# Communications.net
KiCad netlist of a schematic drawn in Altium Designer
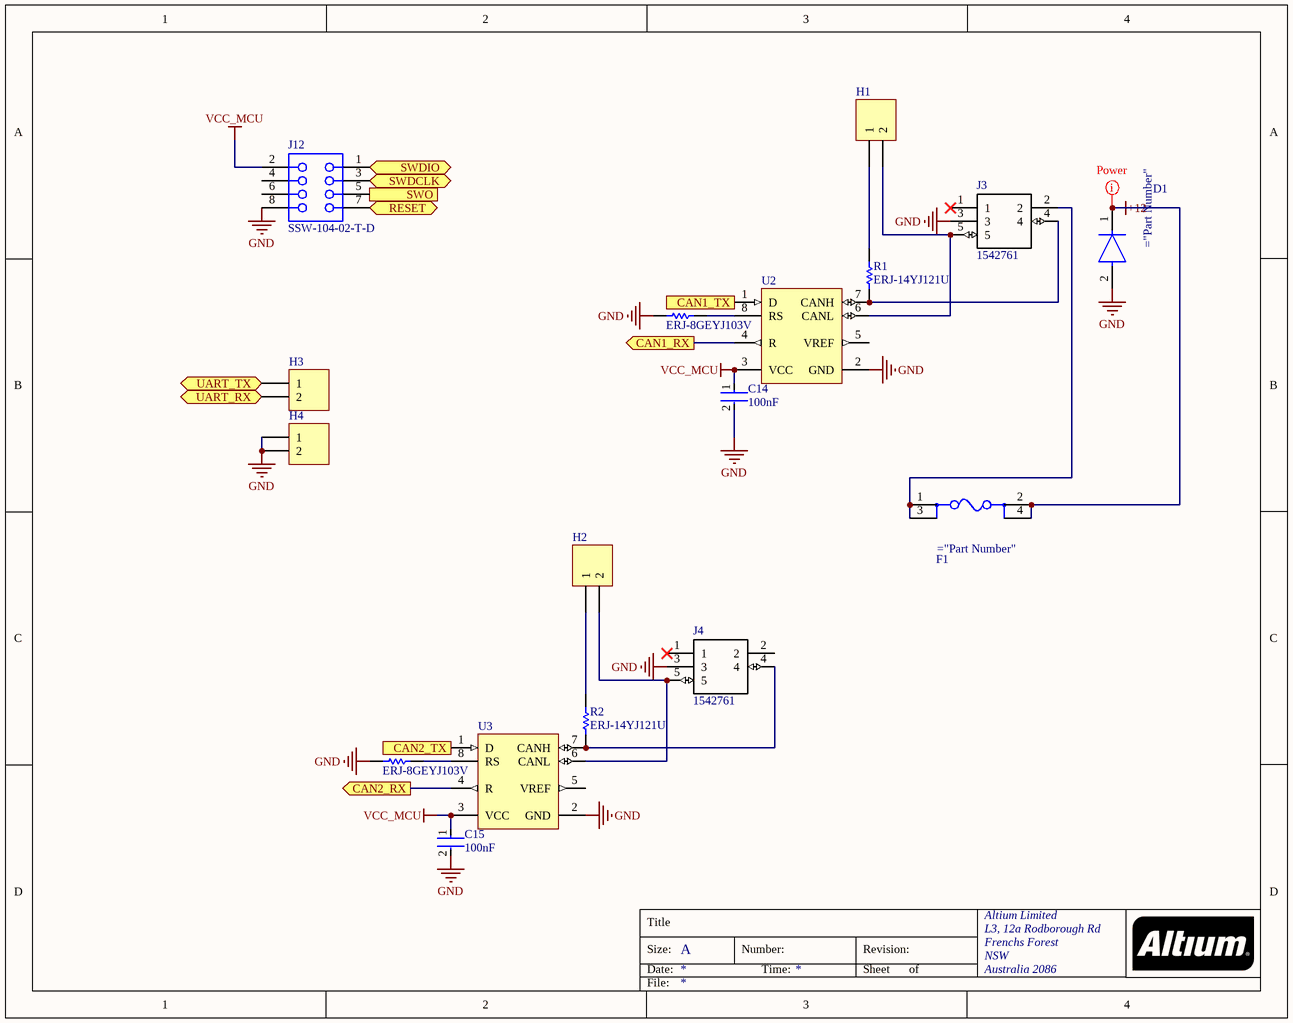
[diagram p0: Communications.SchDoc]

(export (version "E")
  (design (tool "Eeschema 10.0.6"))
  (components
    (comp (ref "C14")
      (value "100nF")
      (footprint "Kemet_C0603_IPC_A")
      (description "CAP CER 0.1UF 100NF 50V X7R 0603 C0603C104K5RACTU")
      (libsource (lib "UNK_Kemet_C0603C104K5RACTU_eec") (part "C0603C104K5RACTU"))
    )
    (comp (ref "C15")
      (value "100nF")
      (footprint "Kemet_C0603_IPC_A")
      (description "CAP CER 0.1UF 100NF 50V X7R 0603 C0603C104K5RACTU")
      (libsource (lib "UNK_Kemet_C0603C104K5RACTU_eec") (part "C0603C104K5RACTU"))
    )
    (comp (ref "D1")
      (value "S1J-13-F")
      (footprint "Diodes_SMA_0")
      (libsource (lib "Diode_Diodes_S1J-13-F_eec") (part "S1J-13-F"))
    )
    (comp (ref "F1")
      (value "3557-2")
      (footprint "Keystone_3557-2_0")
      (libsource (lib "Fuse_Keystone_3557-2_eec") (part "3557-2"))
    )
    (comp (ref "H1")
      (value "Header 0")
      (footprint "HDR1X2")
      (description "Header, 2-Pin")
      (fields (field (name "PUBLISHER") "Altium Limited"))
      (libsource (lib "") (part "Header 2_1"))
    )
    (comp (ref "H2")
      (value "Header 0")
      (footprint "HDR1X2")
      (description "Header, 2-Pin")
      (fields (field (name "PUBLISHER") "Altium Limited"))
      (libsource (lib "") (part "Header 2_1"))
    )
    (comp (ref "H3")
      (value "Header 0")
      (footprint "HDR1X2")
      (description "Header, 2-Pin")
      (fields (field (name "PUBLISHER") "Altium Limited"))
      (libsource (lib "Miscellaneous Connectors") (part "Header 2"))
    )
    (comp (ref "H4")
      (value "Header 0")
      (footprint "HDR1X2")
      (description "Header, 2-Pin")
      (fields (field (name "PUBLISHER") "Altium Limited"))
      (libsource (lib "Miscellaneous Connectors") (part "Header 2"))
    )
    (comp (ref "J3")
      (value "1542761")
      (footprint "SamacSys:1542761")
      (description "Connector")
      (fields (field (name "MOUSER PART NUMBER") "651-1542761") (field (name "RS PART NUMBER") "8025583"))
      (libsource (lib "*") (part "1542761"))
    )
    (comp (ref "J4")
      (value "1542761")
      (footprint "SamacSys:1542761")
      (description "Connector")
      (fields (field (name "MOUSER PART NUMBER") "651-1542761") (field (name "RS PART NUMBER") "8025583"))
      (libsource (lib "*") (part "1542761"))
    )
    (comp (ref "J12")
      (value "SSW-104-02-T-D")
      (footprint "SMTC-SSW-104-02-X-D")
      (description "SQ Post Socket, Through-hole, Vertical, -55 to 105 degC, 2.54mm Pitch, 8-Pin, Female, RoHS")
      (fields (field (name "MANUFACTURER") "Samtec"))
      (libsource (lib "Altium Content Vault") (part "SMTC-SSW-104-X-X-D"))
    )
    (comp (ref "R1")
      (value "ERJ-14YJ121U")
      (footprint "RESC3225X70X50ML20T20")
      (description "120Ohm")
      (fields (field (name "MANUFACTURER") "Panasonic"))
      (libsource (lib "Altium Content Vault") (part "RES"))
    )
    (comp (ref "R2")
      (value "ERJ-14YJ121U")
      (footprint "RESC3225X70X50ML20T20")
      (description "120Ohm")
      (fields (field (name "MANUFACTURER") "Panasonic"))
      (libsource (lib "Altium Content Vault") (part "RES"))
    )
    (comp (ref "R3")
      (value "ERJ-8GEYJ103V")
      (footprint "RESC3216X70X50NL05T20")
      (description "10k")
      (fields (field (name "MANUFACTURER") "Panasonic"))
      (libsource (lib "Altium Content Vault") (part "RES"))
    )
    (comp (ref "R4")
      (value "ERJ-8GEYJ103V")
      (footprint "RESC3216X70X50NL05T20")
      (description "10k")
      (fields (field (name "MANUFACTURER") "Panasonic"))
      (libsource (lib "Altium Content Vault") (part "RES"))
    )
    (comp (ref "U2")
      (value "SN65HVD230D")
      (footprint "D0008A_M")
      (description "CAN Bus Transceiver, 3.3 V, -40 to 85 degC, 8-Pin SOIC (D), Green (RoHS & no Sb/Br), Tube")
      (fields (field (name "GENERIC PART NUMBER") "SN65HVD230"))
      (libsource (lib "Altium Content Vault") (part "TI-SN65HVD230D-SOIC_D-8"))
    )
    (comp (ref "U3")
      (value "SN65HVD230D")
      (footprint "D0008A_M")
      (description "CAN Bus Transceiver, 3.3 V, -40 to 85 degC, 8-Pin SOIC (D), Green (RoHS & no Sb/Br), Tube")
      (fields (field (name "GENERIC PART NUMBER") "SN65HVD230"))
      (libsource (lib "Altium Content Vault") (part "TI-SN65HVD230D-SOIC_D-8"))
    )
  )
  (nets
    (net (code "1") (name "+12") (class "Default")
      (node (ref "D1") (pin "1") (pinfunction "C_1") (pintype "passive"))
      (node (ref "F1") (pin "2") (pinfunction "2_2") (pintype "passive"))
      (node (ref "F1") (pin "4") (pinfunction "4_4") (pintype "passive"))
    )
    (net (code "2") (name "/CAN1_RX") (class "Default")
      (node (ref "U2") (pin "4") (pinfunction "R_4") (pintype "output"))
    )
    (net (code "3") (name "/CAN1_TX") (class "Default")
      (node (ref "U2") (pin "1") (pinfunction "D_1") (pintype "input"))
    )
    (net (code "4") (name "/CAN2_RX") (class "Default")
      (node (ref "U3") (pin "4") (pinfunction "R_4") (pintype "output"))
    )
    (net (code "5") (name "/CAN2_TX") (class "Default")
      (node (ref "U3") (pin "1") (pinfunction "D_1") (pintype "input"))
    )
    (net (code "6") (name "/RESET") (class "Default")
      (node (ref "J12") (pin "7") (pinfunction "7_7") (pintype "passive"))
    )
    (net (code "7") (name "/SWDCLK") (class "Default")
      (node (ref "J12") (pin "3") (pinfunction "3_3") (pintype "passive"))
    )
    (net (code "8") (name "/SWDIO") (class "Default")
      (node (ref "J12") (pin "1") (pinfunction "1_1") (pintype "passive"))
    )
    (net (code "9") (name "/SWO") (class "Default")
      (node (ref "J12") (pin "5") (pinfunction "5_5") (pintype "passive"))
    )
    (net (code "10") (name "/UART_RX") (class "Default")
      (node (ref "H3") (pin "2") (pinfunction "2_2") (pintype "passive"))
    )
    (net (code "11") (name "/UART_TX") (class "Default")
      (node (ref "H3") (pin "1") (pinfunction "1_1") (pintype "passive"))
    )
    (net (code "12") (name "GND") (class "Default")
      (node (ref "C14") (pin "2") (pinfunction "2_2") (pintype "passive"))
      (node (ref "C15") (pin "2") (pinfunction "2_2") (pintype "passive"))
      (node (ref "D1") (pin "2") (pinfunction "A_2") (pintype "passive"))
      (node (ref "H4") (pin "1") (pinfunction "1_1") (pintype "passive"))
      (node (ref "H4") (pin "2") (pinfunction "2_2") (pintype "passive"))
      (node (ref "J12") (pin "8") (pinfunction "8_8") (pintype "passive"))
      (node (ref "J3") (pin "3") (pinfunction "3_3") (pintype "power_in"))
      (node (ref "J4") (pin "3") (pinfunction "3_3") (pintype "power_in"))
      (node (ref "R3") (pin "2") (pinfunction "2_2") (pintype "passive"))
      (node (ref "R4") (pin "2") (pinfunction "2_2") (pintype "passive"))
      (node (ref "U2") (pin "2") (pinfunction "GND_2") (pintype "power_in"))
      (node (ref "U3") (pin "2") (pinfunction "GND_2") (pintype "power_in"))
    )
    (net (code "13") (name "Net-(F1-Pad1)") (class "Default")
      (node (ref "F1") (pin "1") (pinfunction "1_1") (pintype "passive"))
      (node (ref "F1") (pin "3") (pinfunction "3_3") (pintype "passive"))
      (node (ref "J3") (pin "2") (pinfunction "2_2") (pintype "power_in"))
    )
    (net (code "14") (name "Net-(H1-Pad1)") (class "Default")
      (node (ref "H1") (pin "1") (pinfunction "1_1") (pintype "passive"))
      (node (ref "R1") (pin "2") (pinfunction "2_2") (pintype "passive"))
    )
    (net (code "15") (name "Net-(H2-Pad1)") (class "Default")
      (node (ref "H2") (pin "1") (pinfunction "1_1") (pintype "passive"))
      (node (ref "R2") (pin "2") (pinfunction "2_2") (pintype "passive"))
    )
    (net (code "16") (name "Net-(U2-CANH)") (class "Default")
      (node (ref "J3") (pin "4") (pinfunction "4_4") (pintype "bidirectional"))
      (node (ref "R1") (pin "1") (pinfunction "1_1") (pintype "passive"))
      (node (ref "U2") (pin "7") (pinfunction "CANH_7") (pintype "bidirectional"))
    )
    (net (code "17") (name "Net-(U2-CANL)") (class "Default")
      (node (ref "H1") (pin "2") (pinfunction "2_2") (pintype "passive"))
      (node (ref "J3") (pin "5") (pinfunction "5_5") (pintype "bidirectional"))
      (node (ref "U2") (pin "6") (pinfunction "CANL_6") (pintype "bidirectional"))
    )
    (net (code "18") (name "Net-(U2-RS)") (class "Default")
      (node (ref "R3") (pin "1") (pinfunction "1_1") (pintype "passive"))
      (node (ref "U2") (pin "8") (pinfunction "RS_8") (pintype "passive"))
    )
    (net (code "19") (name "Net-(U3-CANH)") (class "Default")
      (node (ref "J4") (pin "4") (pinfunction "4_4") (pintype "bidirectional"))
      (node (ref "R2") (pin "1") (pinfunction "1_1") (pintype "passive"))
      (node (ref "U3") (pin "7") (pinfunction "CANH_7") (pintype "bidirectional"))
    )
    (net (code "20") (name "Net-(U3-CANL)") (class "Default")
      (node (ref "H2") (pin "2") (pinfunction "2_2") (pintype "passive"))
      (node (ref "J4") (pin "5") (pinfunction "5_5") (pintype "bidirectional"))
      (node (ref "U3") (pin "6") (pinfunction "CANL_6") (pintype "bidirectional"))
    )
    (net (code "21") (name "Net-(U3-RS)") (class "Default")
      (node (ref "R4") (pin "1") (pinfunction "1_1") (pintype "passive"))
      (node (ref "U3") (pin "8") (pinfunction "RS_8") (pintype "passive"))
    )
    (net (code "22") (name "VCC_MCU") (class "Default")
      (node (ref "C14") (pin "1") (pinfunction "1_1") (pintype "passive"))
      (node (ref "C15") (pin "1") (pinfunction "1_1") (pintype "passive"))
      (node (ref "J12") (pin "2") (pinfunction "2_2") (pintype "passive"))
      (node (ref "U2") (pin "3") (pinfunction "VCC_3") (pintype "power_in"))
      (node (ref "U3") (pin "3") (pinfunction "VCC_3") (pintype "power_in"))
    )
    (net (code "23") (name "unconnected-(J3-Pad1)") (class "Default")
      (node (ref "J3") (pin "1") (pinfunction "1_1") (pintype "passive+no_connect"))
    )
    (net (code "24") (name "unconnected-(J4-Pad1)") (class "Default")
      (node (ref "J4") (pin "1") (pinfunction "1_1") (pintype "passive+no_connect"))
    )
    (net (code "25") (name "unconnected-(J4-Pad2)") (class "Default")
      (node (ref "J4") (pin "2") (pinfunction "2_2") (pintype "power_in"))
    )
    (net (code "26") (name "unconnected-(J12-Pad4)") (class "Default")
      (node (ref "J12") (pin "4") (pinfunction "4_4") (pintype "passive"))
    )
    (net (code "27") (name "unconnected-(J12-Pad6)") (class "Default")
      (node (ref "J12") (pin "6") (pinfunction "6_6") (pintype "passive"))
    )
    (net (code "28") (name "unconnected-(U2-VREF-Pad5)") (class "Default")
      (node (ref "U2") (pin "5") (pinfunction "VREF_5") (pintype "output"))
    )
    (net (code "29") (name "unconnected-(U3-VREF-Pad5)") (class "Default")
      (node (ref "U3") (pin "5") (pinfunction "VREF_5") (pintype "output"))
    )
  )
)
